# RELAY9.net
KiCad netlist of a schematic drawn in Altium Designer
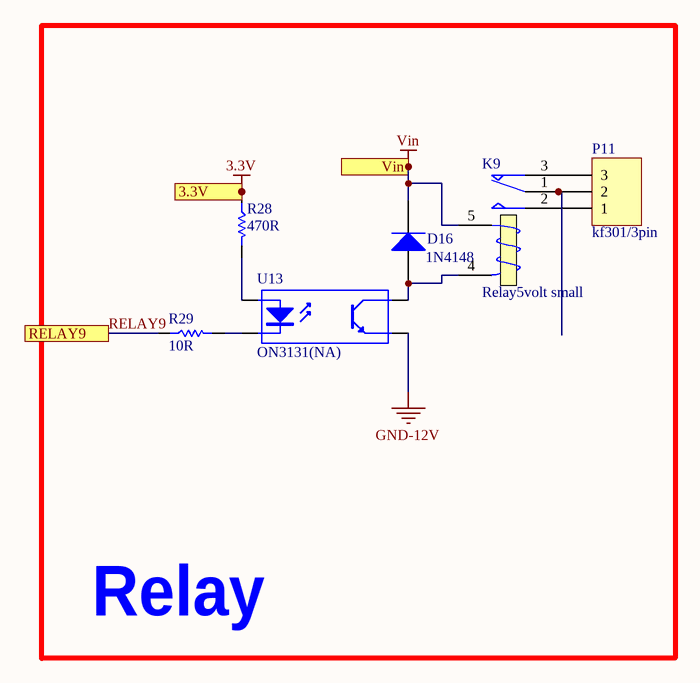
[diagram p0: RELAY9.SchDoc]

(export (version "E")
  (design (tool "Eeschema 10.0.6"))
  (components
    (comp (ref "D16")
      (value "1N4148")
      (footprint "sod123")
      (description "1 Amp General Purpose Rectifier")
      (fields (field (name "PUBLISHER") "Altium Limited"))
      (libsource (lib "Miscellaneous Devices") (part "Diode 1N4007"))
    )
    (comp (ref "K9")
      (value "Relay5volt small")
      (footprint "relay5_childern")
      (description "SPDT Relay")
      (fields (field (name "PUBLISHER") "Altium Limited"))
      (libsource (lib "FLIB") (part "Relay"))
    )
    (comp (ref "P11")
      (value "kf301/3pin")
      (footprint "Blue Connector 1*3 -kf301")
      (fields (field (name "PUBLISHER") "Altium Limited"))
      (libsource (lib "Miscellaneous Connectors") (part "Header 3"))
    )
    (comp (ref "R28")
      (value "470R")
      (footprint "0805/resistor")
      (description "Resistor")
      (fields (field (name "TOLERANCE") "5%") (field (name "POWER") "1/8 W"))
      (libsource (lib "skille") (part "Resistor"))
    )
    (comp (ref "R29")
      (value "10R")
      (footprint "0805/resistor")
      (description "Resistor")
      (fields (field (name "TOLERANCE") "5%") (field (name "POWER") "1/8 W"))
      (libsource (lib "skille") (part "Resistor"))
    )
    (comp (ref "U13")
      (value "ON3131(NA)")
      (footprint "OPTO_COUPLER")
      (description "4-Pin Phototransistor Optocoupler")
      (fields (field (name "PUBLISHER") "Altium Limited"))
      (libsource (lib "skille") (part "Optoisolator1"))
    )
  )
  (nets
    (net (code "1") (name "/RELAY9") (class "Default")
      (node (ref "R29") (pin "1") (pinfunction "1_1") (pintype "passive"))
    )
    (net (code "2") (name "3.3V") (class "Default")
      (node (ref "R28") (pin "1") (pinfunction "1_1") (pintype "passive"))
    )
    (net (code "3") (name "GND-12V") (class "Default")
      (node (ref "U13") (pin "3") (pinfunction "E_3") (pintype "passive"))
    )
    (net (code "4") (name "Net-(K9-COM)") (class "Default")
      (node (ref "K9") (pin "1") (pinfunction "COM_1") (pintype "passive"))
      (node (ref "P11") (pin "2") (pinfunction "2_2") (pintype "passive"))
    )
    (net (code "5") (name "Net-(K9-NO)") (class "Default")
      (node (ref "K9") (pin "2") (pinfunction "NO_2") (pintype "passive"))
      (node (ref "P11") (pin "1") (pinfunction "1_1") (pintype "passive"))
    )
    (net (code "6") (name "Net-(K9-T1)") (class "Default")
      (node (ref "K9") (pin "3") (pinfunction "T1_3") (pintype "passive"))
      (node (ref "P11") (pin "3") (pinfunction "3_3") (pintype "passive"))
    )
    (net (code "7") (name "Net-(K9-T2)") (class "Default")
      (node (ref "D16") (pin "A") (pinfunction "A_A") (pintype "passive"))
      (node (ref "K9") (pin "4") (pinfunction "T2_4") (pintype "passive"))
      (node (ref "U13") (pin "4") (pinfunction "C_4") (pintype "passive"))
    )
    (net (code "8") (name "Net-(U13-A)") (class "Default")
      (node (ref "R28") (pin "2") (pinfunction "2_2") (pintype "passive"))
      (node (ref "U13") (pin "1") (pinfunction "A_1") (pintype "passive"))
    )
    (net (code "9") (name "Net-(U13-K)") (class "Default")
      (node (ref "R29") (pin "2") (pinfunction "2_2") (pintype "passive"))
      (node (ref "U13") (pin "2") (pinfunction "K_2") (pintype "passive"))
    )
    (net (code "10") (name "Vin") (class "Default")
      (node (ref "D16") (pin "K") (pinfunction "K_K") (pintype "passive"))
      (node (ref "K9") (pin "5") (pinfunction "5_5") (pintype "passive"))
    )
  )
)
